# MySens-GWeasyRS485-Nano-V02-003.net
KiCad netlist of a schematic drawn in EAGLE
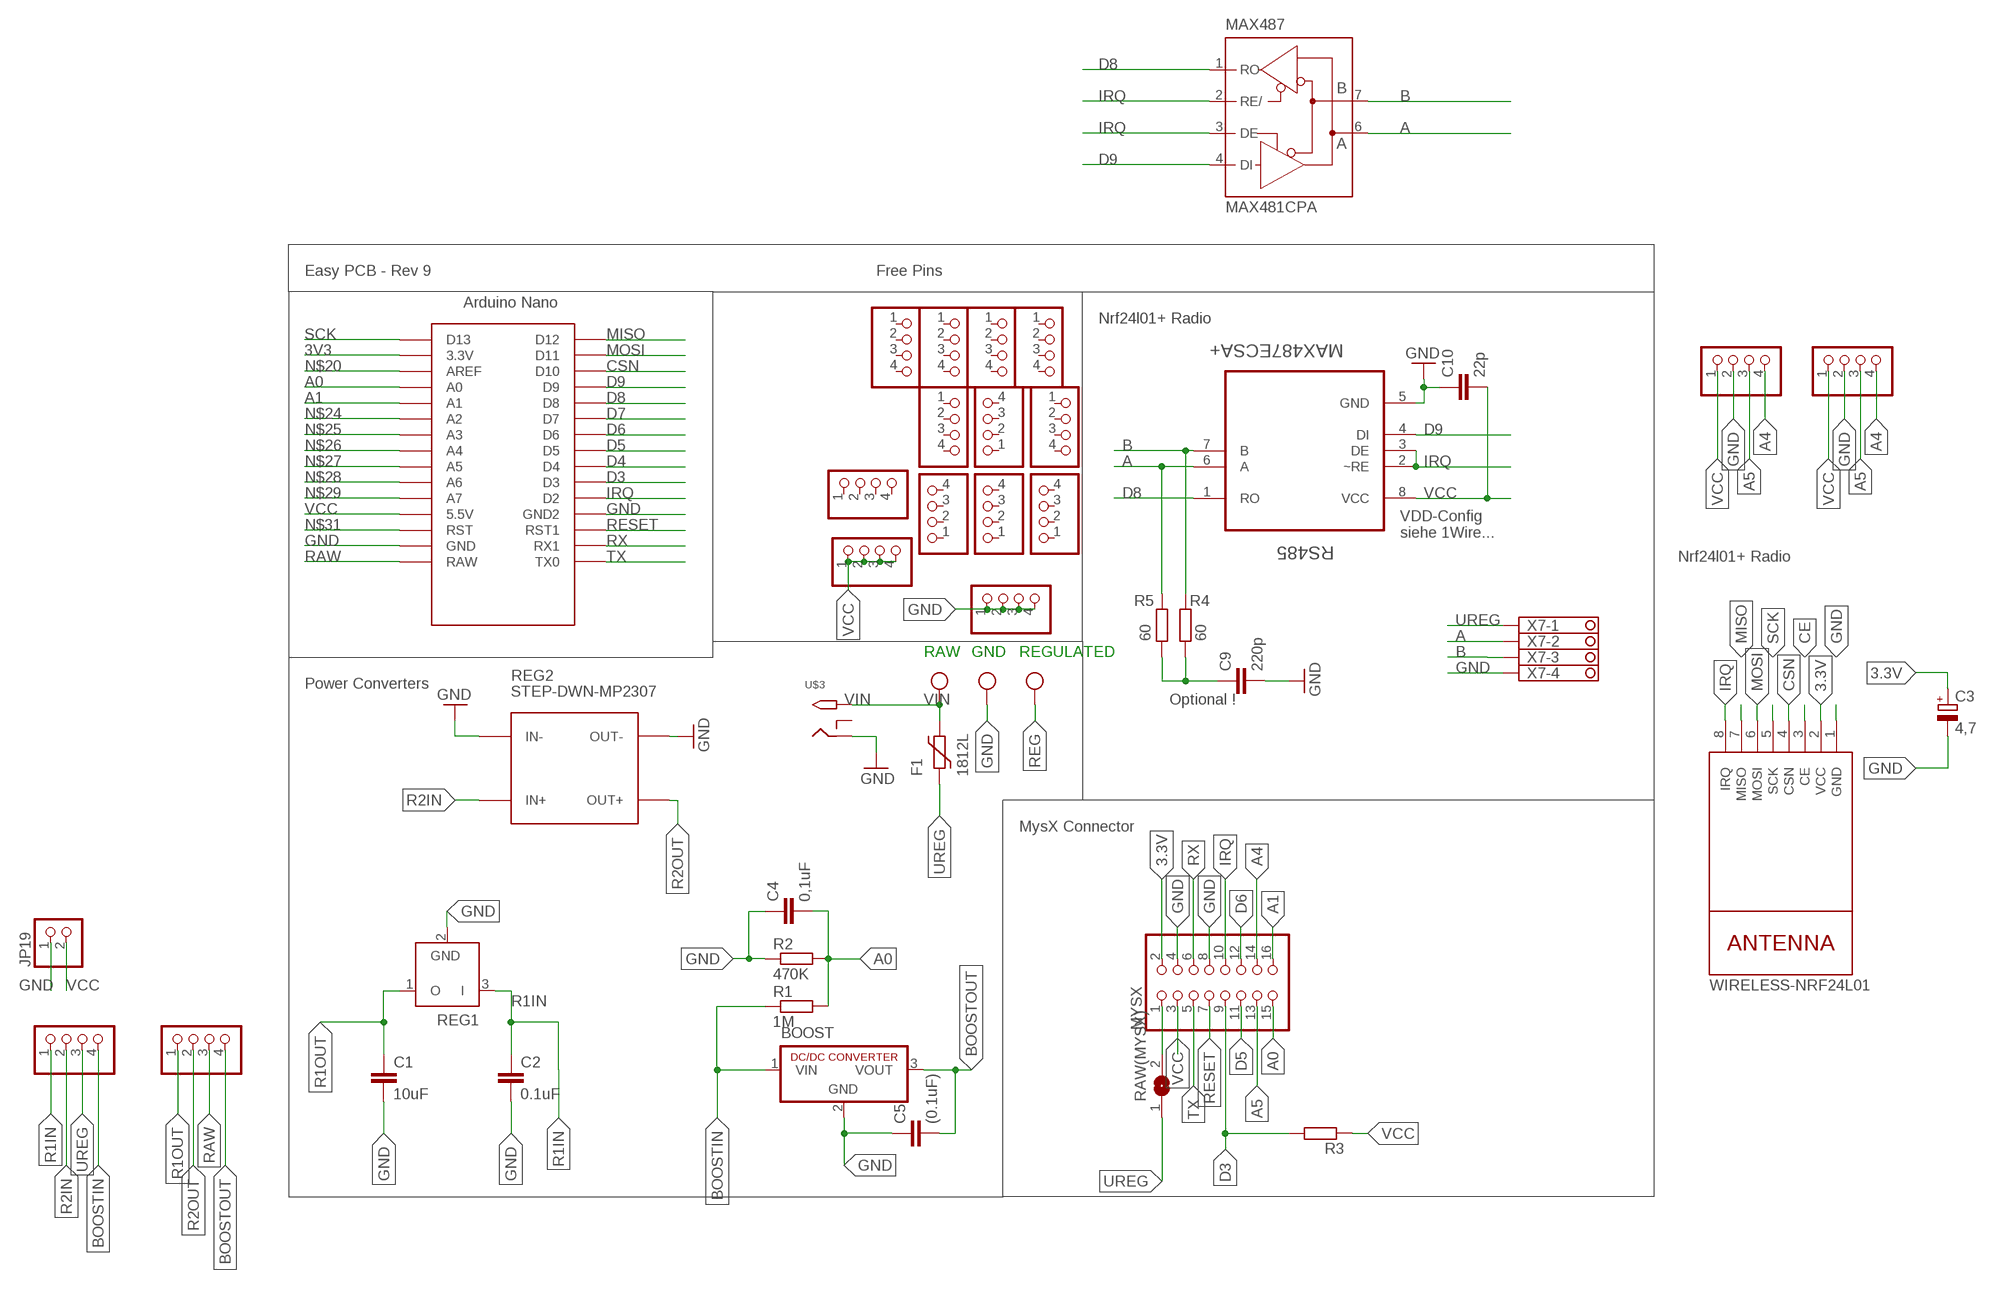
[diagram p0: schematic, sheet 1]

(export (version "E")
  (design (tool "Eeschema 10.0.6"))
  (components
    (comp (ref "BOOST")
      (value "R-78C1.8-1.0")
      (footprint "eagle-import:SIP3")
      (libsource (lib "eagle-import") (part "R-78C-1.01.8"))
    )
    (comp (ref "C1")
      (value "10uF")
      (footprint "eagle-import:C1210")
      (libsource (lib "eagle-import") (part "C-EUC1210"))
    )
    (comp (ref "C2")
      (value "0.1uF")
      (footprint "eagle-import:C1206")
      (libsource (lib "eagle-import") (part "C-EUC1206"))
    )
    (comp (ref "C3")
      (value "4,7")
      (footprint "eagle-import:SMC_C")
      (libsource (lib "eagle-import") (part "CPOL-EUSMCC"))
    )
    (comp (ref "C4")
      (value "0,1uF")
      (footprint "eagle-import:C1206")
      (libsource (lib "eagle-import") (part "C-EUC1206"))
    )
    (comp (ref "C5")
      (value "(0.1uF)")
      (footprint "eagle-import:C1206")
      (libsource (lib "eagle-import") (part "C-EUC1206"))
    )
    (comp (ref "C9")
      (value "220p")
      (footprint "eagle-import:C0805")
      (libsource (lib "eagle-import") (part "C-EUC0805"))
    )
    (comp (ref "C10")
      (value "22p")
      (footprint "eagle-import:C0805")
      (libsource (lib "eagle-import") (part "C-EUC0805"))
    )
    (comp (ref "F1")
      (value "1812L")
      (footprint "eagle-import:1812L")
      (libsource (lib "eagle-import") (part "1812L"))
    )
    (comp (ref "JP1")
      (value "PINHD-1X04_2.54-S")
      (footprint "eagle-import:1X04-S")
      (libsource (lib "eagle-import") (part "PINHD-1X04_2.54-S"))
    )
    (comp (ref "JP2")
      (value "PINHD-1X04_2.54-S")
      (footprint "eagle-import:1X04-S")
      (libsource (lib "eagle-import") (part "PINHD-1X04_2.54-S"))
    )
    (comp (ref "JP3")
      (value "PINHD-1X04_2.54-S")
      (footprint "eagle-import:1X04-S")
      (libsource (lib "eagle-import") (part "PINHD-1X04_2.54-S"))
    )
    (comp (ref "JP4")
      (value "PINHD-1X04_2.54-S")
      (footprint "eagle-import:1X04-S")
      (libsource (lib "eagle-import") (part "PINHD-1X04_2.54-S"))
    )
    (comp (ref "JP5")
      (value "PINHD-1X04_2.54-S")
      (footprint "eagle-import:1X04-S")
      (libsource (lib "eagle-import") (part "PINHD-1X04_2.54-S"))
    )
    (comp (ref "JP6")
      (value "PINHD-1X04_2.54-S")
      (footprint "eagle-import:1X04-S")
      (libsource (lib "eagle-import") (part "PINHD-1X04_2.54-S"))
    )
    (comp (ref "JP7")
      (value "PINHD-1X04_2.54-S")
      (footprint "eagle-import:1X04-S")
      (libsource (lib "eagle-import") (part "PINHD-1X04_2.54-S"))
    )
    (comp (ref "JP9")
      (value "PINHD-1X04_2.54-S")
      (footprint "eagle-import:1X04-S")
      (libsource (lib "eagle-import") (part "PINHD-1X04_2.54-S"))
    )
    (comp (ref "JP10")
      (value "PINHD-1X04_2.54-S")
      (footprint "eagle-import:1X04-S")
      (libsource (lib "eagle-import") (part "PINHD-1X04_2.54-S"))
    )
    (comp (ref "JP11")
      (value "PINHD-1X04_2.54-S")
      (footprint "eagle-import:1X04-S")
      (libsource (lib "eagle-import") (part "PINHD-1X04_2.54-S"))
    )
    (comp (ref "JP12")
      (value "PINHD-1X04_2.54-S")
      (footprint "eagle-import:1X04-S")
      (libsource (lib "eagle-import") (part "PINHD-1X04_2.54-S"))
    )
    (comp (ref "JP13")
      (value "PINHD-1X04_2.54-S")
      (footprint "eagle-import:1X04-S")
      (libsource (lib "eagle-import") (part "PINHD-1X04_2.54-S"))
    )
    (comp (ref "JP14")
      (value "PINHD-1X04_2.54-S")
      (footprint "eagle-import:1X04-S")
      (libsource (lib "eagle-import") (part "PINHD-1X04_2.54-S"))
    )
    (comp (ref "JP15")
      (value "PINHD-1X04_2.54-S")
      (footprint "eagle-import:1X04-S")
      (libsource (lib "eagle-import") (part "PINHD-1X04_2.54-S"))
    )
    (comp (ref "JP16")
      (value "PINHD-1X04_2.54-S")
      (footprint "eagle-import:1X04-S")
      (libsource (lib "eagle-import") (part "PINHD-1X04_2.54-S"))
    )
    (comp (ref "JP17")
      (value "PINHD-1X04_2.54-S")
      (footprint "eagle-import:1X04-S")
      (libsource (lib "eagle-import") (part "PINHD-1X04_2.54-S"))
    )
    (comp (ref "JP18")
      (value "PINHD-1X04_2.54-S")
      (footprint "eagle-import:1X04-S")
      (libsource (lib "eagle-import") (part "PINHD-1X04_2.54-S"))
    )
    (comp (ref "JP19")
      (value "PINHD-1X2")
      (footprint "eagle-import:1X02")
      (libsource (lib "eagle-import") (part "PINHD-1X2"))
    )
    (comp (ref "MAX487")
      (value "MAX481CPA")
      (footprint "eagle-import:DIL08")
      (libsource (lib "eagle-import") (part "MAX481CPA"))
    )
    (comp (ref "MYSX")
      (value "PINHD-2X08_2.54")
      (footprint "eagle-import:2X08")
      (libsource (lib "eagle-import") (part "PINHD-2X08_2.54"))
    )
    (comp (ref "NRF24L01+")
      (value "WIRELESS-NRF24L01")
      (footprint "eagle-import:WIRELESS-NRF24L01")
      (libsource (lib "eagle-import") (part "WIRELESS-NRF24L01"))
    )
    (comp (ref "R1")
      (value "1M")
      (footprint "eagle-import:R0805")
      (libsource (lib "eagle-import") (part "R-EU_R0805"))
    )
    (comp (ref "R2")
      (value "470K")
      (footprint "eagle-import:R0805")
      (libsource (lib "eagle-import") (part "R-EU_R0805"))
    )
    (comp (ref "R3")
      (value "R-EU_R0805")
      (footprint "eagle-import:R0805")
      (libsource (lib "eagle-import") (part "R-EU_R0805"))
    )
    (comp (ref "R4")
      (value "60")
      (footprint "eagle-import:R0805")
      (libsource (lib "eagle-import") (part "R-EU_R0805"))
    )
    (comp (ref "R5")
      (value "60")
      (footprint "eagle-import:R0805")
      (libsource (lib "eagle-import") (part "R-EU_R0805"))
    )
    (comp (ref "RAW(MYSX)")
      (value "SJ")
      (footprint "eagle-import:SJ")
      (libsource (lib "eagle-import") (part "SJ"))
    )
    (comp (ref "REG1")
      (value "LP2950Z")
      (footprint "eagle-import:TO92")
      (libsource (lib "eagle-import") (part "LP2950Z"))
    )
    (comp (ref "REG2")
      (value "STEP-DWN-MP2307")
      (footprint "eagle-import:DC-DC-STEP-DOWN-MP2307")
      (libsource (lib "eagle-import") (part "DC-DC-STEP-DOWN-MP2307"))
    )
    (comp (ref "REGULATED")
      (value "W237-103")
      (footprint "eagle-import:W237-103")
      (fields (field (name "MPN") "237-103"))
      (libsource (lib "eagle-import") (part "W237-103"))
    )
    (comp (ref "RS485")
      (value "MAX487ECSA+")
      (footprint "eagle-import:SOIC127P600X175-8N")
      (libsource (lib "eagle-import") (part "MAX487ECSA+"))
    )
    (comp (ref "U$2")
      (value "NANO")
      (footprint "eagle-import:NANO")
      (libsource (lib "eagle-import") (part "NANO"))
    )
    (comp (ref "U$3")
      (value "2.1MMJACKTHM")
      (footprint "eagle-import:PJ-102A")
      (libsource (lib "eagle-import") (part "2.1MMJACKTHM"))
    )
    (comp (ref "X7")
      (value "1751264")
      (footprint "eagle-import:1751264")
      (libsource (lib "eagle-import") (part "1751264"))
    )
  )
  (nets
    (net (code "1") (name "/3V3") (class "Default")
      (node (ref "U$2") (pin "3.3V") (pinfunction "3.3V_3.3V") (pintype "bidirectional"))
    )
    (net (code "2") (name "/A") (class "Default")
      (node (ref "MAX487") (pin "6") (pinfunction "A_6") (pintype "passive"))
      (node (ref "R5") (pin "2") (pinfunction "2_2") (pintype "passive"))
      (node (ref "RS485") (pin "6") (pinfunction "A_6") (pintype "bidirectional"))
      (node (ref "X7") (pin "2") (pinfunction "K_2") (pintype "passive"))
    )
    (net (code "3") (name "/B") (class "Default")
      (node (ref "MAX487") (pin "7") (pinfunction "B_7") (pintype "passive"))
      (node (ref "R4") (pin "2") (pinfunction "2_2") (pintype "passive"))
      (node (ref "RS485") (pin "7") (pinfunction "B_7") (pintype "bidirectional"))
      (node (ref "X7") (pin "3") (pinfunction "K_3") (pintype "passive"))
    )
    (net (code "4") (name "/D4") (class "Default")
      (node (ref "U$2") (pin "D4") (pinfunction "D4_D4") (pintype "bidirectional"))
    )
    (net (code "5") (name "/D7") (class "Default")
      (node (ref "U$2") (pin "D7") (pinfunction "D7_D7") (pintype "bidirectional"))
    )
    (net (code "6") (name "/D8") (class "Default")
      (node (ref "MAX487") (pin "1") (pinfunction "RO_1") (pintype "output"))
      (node (ref "RS485") (pin "1") (pinfunction "RO_1") (pintype "output"))
      (node (ref "U$2") (pin "D8") (pinfunction "D8_D8") (pintype "bidirectional"))
    )
    (net (code "7") (name "/D9") (class "Default")
      (node (ref "MAX487") (pin "4") (pinfunction "DI_4") (pintype "input"))
      (node (ref "RS485") (pin "4") (pinfunction "DI_4") (pintype "input"))
      (node (ref "U$2") (pin "D9") (pinfunction "D9_D9") (pintype "bidirectional"))
    )
    (net (code "8") (name "/N$20") (class "Default")
      (node (ref "U$2") (pin "AREF") (pinfunction "AREF_AREF") (pintype "bidirectional"))
    )
    (net (code "9") (name "/N$24") (class "Default")
      (node (ref "U$2") (pin "A2") (pinfunction "A2_A2") (pintype "bidirectional"))
    )
    (net (code "10") (name "/N$25") (class "Default")
      (node (ref "U$2") (pin "A3") (pinfunction "A3_A3") (pintype "bidirectional"))
    )
    (net (code "11") (name "/N$26") (class "Default")
      (node (ref "U$2") (pin "A4") (pinfunction "A4_A4") (pintype "bidirectional"))
    )
    (net (code "12") (name "/N$27") (class "Default")
      (node (ref "U$2") (pin "A5") (pinfunction "A5_A5") (pintype "bidirectional"))
    )
    (net (code "13") (name "/N$28") (class "Default")
      (node (ref "U$2") (pin "A6") (pinfunction "A6_A6") (pintype "bidirectional"))
    )
    (net (code "14") (name "/N$29") (class "Default")
      (node (ref "U$2") (pin "A7") (pinfunction "A7_A7") (pintype "bidirectional"))
    )
    (net (code "15") (name "/N$31") (class "Default")
      (node (ref "U$2") (pin "RST") (pinfunction "RST_RST") (pintype "bidirectional"))
    )
    (net (code "16") (name "/VIN") (class "Default")
      (node (ref "F1") (pin "P$2") (pinfunction "2_P$2") (pintype "passive"))
      (node (ref "REGULATED") (pin "3") (pinfunction "KL_3") (pintype "passive"))
      (node (ref "U$3") (pin "TIP") (pinfunction "TIP_TIP") (pintype "bidirectional"))
    )
    (net (code "17") (name "3.3V") (class "Default")
      (node (ref "C3") (pin "+") (pinfunction "+_+") (pintype "passive"))
      (node (ref "MYSX") (pin "2") (pinfunction "2_2") (pintype "passive"))
      (node (ref "NRF24L01+") (pin "2") (pinfunction "VCC_2") (pintype "power_in"))
    )
    (net (code "18") (name "A0") (class "Default")
      (node (ref "C4") (pin "2") (pinfunction "2_2") (pintype "passive"))
      (node (ref "MYSX") (pin "15") (pinfunction "15_15") (pintype "passive"))
      (node (ref "R1") (pin "2") (pinfunction "2_2") (pintype "passive"))
      (node (ref "R2") (pin "2") (pinfunction "2_2") (pintype "passive"))
      (node (ref "U$2") (pin "A0") (pinfunction "A0_A0") (pintype "bidirectional"))
    )
    (net (code "19") (name "A1") (class "Default")
      (node (ref "MYSX") (pin "16") (pinfunction "16_16") (pintype "passive"))
      (node (ref "U$2") (pin "A1") (pinfunction "A1_A1") (pintype "bidirectional"))
    )
    (net (code "20") (name "A4") (class "Default")
      (node (ref "JP10") (pin "4") (pinfunction "4_4") (pintype "passive"))
      (node (ref "JP6") (pin "4") (pinfunction "4_4") (pintype "passive"))
      (node (ref "MYSX") (pin "14") (pinfunction "14_14") (pintype "passive"))
    )
    (net (code "21") (name "A5") (class "Default")
      (node (ref "JP10") (pin "3") (pinfunction "3_3") (pintype "passive"))
      (node (ref "JP6") (pin "3") (pinfunction "3_3") (pintype "passive"))
      (node (ref "MYSX") (pin "13") (pinfunction "13_13") (pintype "passive"))
    )
    (net (code "22") (name "BOOSTIN") (class "Default")
      (node (ref "BOOST") (pin "1") (pinfunction "VIN_1") (pintype "passive"))
      (node (ref "JP2") (pin "4") (pinfunction "4_4") (pintype "passive"))
      (node (ref "R1") (pin "1") (pinfunction "1_1") (pintype "passive"))
    )
    (net (code "23") (name "BOOSTOUT") (class "Default")
      (node (ref "BOOST") (pin "3") (pinfunction "VOUT_3") (pintype "passive"))
      (node (ref "C5") (pin "2") (pinfunction "2_2") (pintype "passive"))
      (node (ref "JP4") (pin "4") (pinfunction "4_4") (pintype "passive"))
    )
    (net (code "24") (name "CE") (class "Default")
      (node (ref "NRF24L01+") (pin "3") (pinfunction "CE_3") (pintype "bidirectional"))
    )
    (net (code "25") (name "CSN") (class "Default")
      (node (ref "NRF24L01+") (pin "4") (pinfunction "CSN_4") (pintype "bidirectional"))
      (node (ref "U$2") (pin "D10") (pinfunction "D10_D10") (pintype "bidirectional"))
    )
    (net (code "26") (name "D3") (class "Default")
      (node (ref "MYSX") (pin "9") (pinfunction "9_9") (pintype "passive"))
      (node (ref "R3") (pin "2") (pinfunction "2_2") (pintype "passive"))
      (node (ref "U$2") (pin "D3") (pinfunction "D3_D3") (pintype "bidirectional"))
    )
    (net (code "27") (name "D5") (class "Default")
      (node (ref "MYSX") (pin "11") (pinfunction "11_11") (pintype "passive"))
      (node (ref "U$2") (pin "D5") (pinfunction "D5_D5") (pintype "bidirectional"))
    )
    (net (code "28") (name "D6") (class "Default")
      (node (ref "MYSX") (pin "12") (pinfunction "12_12") (pintype "passive"))
      (node (ref "U$2") (pin "D6") (pinfunction "D6_D6") (pintype "bidirectional"))
    )
    (net (code "29") (name "GND") (class "Default")
      (node (ref "BOOST") (pin "2") (pinfunction "GND_2") (pintype "passive"))
      (node (ref "C1") (pin "2") (pinfunction "2_2") (pintype "passive"))
      (node (ref "C10") (pin "1") (pinfunction "1_1") (pintype "passive"))
      (node (ref "C2") (pin "2") (pinfunction "2_2") (pintype "passive"))
      (node (ref "C3") (pin "-") (pinfunction "-_-") (pintype "passive"))
      (node (ref "C4") (pin "1") (pinfunction "1_1") (pintype "passive"))
      (node (ref "C5") (pin "1") (pinfunction "1_1") (pintype "passive"))
      (node (ref "C9") (pin "2") (pinfunction "2_2") (pintype "passive"))
      (node (ref "JP1") (pin "1") (pinfunction "1_1") (pintype "passive"))
      (node (ref "JP1") (pin "2") (pinfunction "2_2") (pintype "passive"))
      (node (ref "JP1") (pin "3") (pinfunction "3_3") (pintype "passive"))
      (node (ref "JP1") (pin "4") (pinfunction "4_4") (pintype "passive"))
      (node (ref "JP10") (pin "2") (pinfunction "2_2") (pintype "passive"))
      (node (ref "JP19") (pin "1") (pinfunction "1_1") (pintype "passive"))
      (node (ref "JP6") (pin "2") (pinfunction "2_2") (pintype "passive"))
      (node (ref "MYSX") (pin "4") (pinfunction "4_4") (pintype "passive"))
      (node (ref "MYSX") (pin "8") (pinfunction "8_8") (pintype "passive"))
      (node (ref "NRF24L01+") (pin "1") (pinfunction "GND_1") (pintype "power_in"))
      (node (ref "R2") (pin "1") (pinfunction "1_1") (pintype "passive"))
      (node (ref "REG1") (pin "2") (pinfunction "GND_2") (pintype "power_in"))
      (node (ref "REG2") (pin "IN-") (pinfunction "IN-_IN-") (pintype "bidirectional"))
      (node (ref "REG2") (pin "OUT-") (pinfunction "OUT-_OUT-") (pintype "bidirectional"))
      (node (ref "REGULATED") (pin "2") (pinfunction "KL_2") (pintype "passive"))
      (node (ref "RS485") (pin "5") (pinfunction "GND_5") (pintype "passive"))
      (node (ref "U$2") (pin "GND") (pinfunction "GND_GND") (pintype "bidirectional"))
      (node (ref "U$2") (pin "GND1") (pinfunction "GND2_GND1") (pintype "bidirectional"))
      (node (ref "U$3") (pin "RING") (pinfunction "RING_RING") (pintype "bidirectional"))
      (node (ref "X7") (pin "4") (pinfunction "K_4") (pintype "passive"))
    )
    (net (code "30") (name "IRQ") (class "Default")
      (node (ref "MAX487") (pin "2") (pinfunction "RE/_2") (pintype "input"))
      (node (ref "MAX487") (pin "3") (pinfunction "DE_3") (pintype "input"))
      (node (ref "MYSX") (pin "10") (pinfunction "10_10") (pintype "passive"))
      (node (ref "NRF24L01+") (pin "8") (pinfunction "IRQ_8") (pintype "bidirectional"))
      (node (ref "RS485") (pin "2") (pinfunction "~{RE}_2") (pintype "input"))
      (node (ref "RS485") (pin "3") (pinfunction "DE_3") (pintype "input"))
      (node (ref "U$2") (pin "D2") (pinfunction "D2_D2") (pintype "bidirectional"))
    )
    (net (code "31") (name "MISO") (class "Default")
      (node (ref "NRF24L01+") (pin "7") (pinfunction "MISO_7") (pintype "bidirectional"))
      (node (ref "U$2") (pin "D12") (pinfunction "D12_D12") (pintype "bidirectional"))
    )
    (net (code "32") (name "MOSI") (class "Default")
      (node (ref "NRF24L01+") (pin "6") (pinfunction "MOSI_6") (pintype "bidirectional"))
      (node (ref "U$2") (pin "D11") (pinfunction "D11_D11") (pintype "bidirectional"))
    )
    (net (code "33") (name "Net-(C9-Pad1)") (class "Default")
      (node (ref "C9") (pin "1") (pinfunction "1_1") (pintype "passive"))
      (node (ref "R4") (pin "1") (pinfunction "1_1") (pintype "passive"))
      (node (ref "R5") (pin "1") (pinfunction "1_1") (pintype "passive"))
    )
    (net (code "34") (name "Net-(MYSX-Pad1)") (class "Default")
      (node (ref "MYSX") (pin "1") (pinfunction "1_1") (pintype "passive"))
      (node (ref "RAW(MYSX)") (pin "2") (pinfunction "2_2") (pintype "passive"))
    )
    (net (code "35") (name "R1IN") (class "Default")
      (node (ref "C2") (pin "1") (pinfunction "1_1") (pintype "passive"))
      (node (ref "JP2") (pin "1") (pinfunction "1_1") (pintype "passive"))
      (node (ref "REG1") (pin "3") (pinfunction "I_3") (pintype "input"))
    )
    (net (code "36") (name "R1OUT") (class "Default")
      (node (ref "C1") (pin "1") (pinfunction "1_1") (pintype "passive"))
      (node (ref "JP4") (pin "1") (pinfunction "1_1") (pintype "passive"))
      (node (ref "REG1") (pin "1") (pinfunction "O_1") (pintype "input"))
    )
    (net (code "37") (name "R2IN") (class "Default")
      (node (ref "JP2") (pin "2") (pinfunction "2_2") (pintype "passive"))
      (node (ref "REG2") (pin "IN+") (pinfunction "IN+_IN+") (pintype "bidirectional"))
    )
    (net (code "38") (name "R2OUT") (class "Default")
      (node (ref "JP4") (pin "2") (pinfunction "2_2") (pintype "passive"))
      (node (ref "REG2") (pin "OUT+") (pinfunction "OUT+_OUT+") (pintype "bidirectional"))
    )
    (net (code "39") (name "RAW") (class "Default")
      (node (ref "JP4") (pin "3") (pinfunction "3_3") (pintype "passive"))
      (node (ref "U$2") (pin "RAW") (pinfunction "RAW_RAW") (pintype "bidirectional"))
    )
    (net (code "40") (name "REG") (class "Default")
      (node (ref "REGULATED") (pin "1") (pinfunction "KL_1") (pintype "passive"))
    )
    (net (code "41") (name "RESET") (class "Default")
      (node (ref "MYSX") (pin "7") (pinfunction "7_7") (pintype "passive"))
      (node (ref "U$2") (pin "RST1") (pinfunction "RST1_RST1") (pintype "bidirectional"))
    )
    (net (code "42") (name "RX") (class "Default")
      (node (ref "MYSX") (pin "6") (pinfunction "6_6") (pintype "passive"))
      (node (ref "U$2") (pin "RX1") (pinfunction "RX1_RX1") (pintype "bidirectional"))
    )
    (net (code "43") (name "SCK") (class "Default")
      (node (ref "NRF24L01+") (pin "5") (pinfunction "SCK_5") (pintype "bidirectional"))
      (node (ref "U$2") (pin "D13") (pinfunction "D13_D13") (pintype "bidirectional"))
    )
    (net (code "44") (name "TX") (class "Default")
      (node (ref "MYSX") (pin "5") (pinfunction "5_5") (pintype "passive"))
      (node (ref "U$2") (pin "TX0") (pinfunction "TX0_TX0") (pintype "bidirectional"))
    )
    (net (code "45") (name "UREG") (class "Default")
      (node (ref "F1") (pin "P$1") (pinfunction "1_P$1") (pintype "passive"))
      (node (ref "JP2") (pin "3") (pinfunction "3_3") (pintype "passive"))
      (node (ref "RAW(MYSX)") (pin "1") (pinfunction "1_1") (pintype "passive"))
      (node (ref "X7") (pin "1") (pinfunction "K_1") (pintype "passive"))
    )
    (net (code "46") (name "VCC") (class "Default")
      (node (ref "C10") (pin "2") (pinfunction "2_2") (pintype "passive"))
      (node (ref "JP10") (pin "1") (pinfunction "1_1") (pintype "passive"))
      (node (ref "JP19") (pin "2") (pinfunction "2_2") (pintype "passive"))
      (node (ref "JP3") (pin "1") (pinfunction "1_1") (pintype "passive"))
      (node (ref "JP3") (pin "2") (pinfunction "2_2") (pintype "passive"))
      (node (ref "JP3") (pin "3") (pinfunction "3_3") (pintype "passive"))
      (node (ref "JP3") (pin "4") (pinfunction "4_4") (pintype "passive"))
      (node (ref "JP6") (pin "1") (pinfunction "1_1") (pintype "passive"))
      (node (ref "MYSX") (pin "3") (pinfunction "3_3") (pintype "passive"))
      (node (ref "R3") (pin "1") (pinfunction "1_1") (pintype "passive"))
      (node (ref "RS485") (pin "8") (pinfunction "VCC_8") (pintype "power_in"))
      (node (ref "U$2") (pin "5V") (pinfunction "5.5V_5V") (pintype "bidirectional"))
    )
    (net (code "47") (name "unconnected-(JP5-Pad1)") (class "Default")
      (node (ref "JP5") (pin "1") (pinfunction "1_1") (pintype "passive"))
    )
    (net (code "48") (name "unconnected-(JP5-Pad2)") (class "Default")
      (node (ref "JP5") (pin "2") (pinfunction "2_2") (pintype "passive"))
    )
    (net (code "49") (name "unconnected-(JP5-Pad3)") (class "Default")
      (node (ref "JP5") (pin "3") (pinfunction "3_3") (pintype "passive"))
    )
    (net (code "50") (name "unconnected-(JP5-Pad4)") (class "Default")
      (node (ref "JP5") (pin "4") (pinfunction "4_4") (pintype "passive"))
    )
    (net (code "51") (name "unconnected-(JP7-Pad1)") (class "Default")
      (node (ref "JP7") (pin "1") (pinfunction "1_1") (pintype "passive"))
    )
    (net (code "52") (name "unconnected-(JP7-Pad2)") (class "Default")
      (node (ref "JP7") (pin "2") (pinfunction "2_2") (pintype "passive"))
    )
    (net (code "53") (name "unconnected-(JP7-Pad3)") (class "Default")
      (node (ref "JP7") (pin "3") (pinfunction "3_3") (pintype "passive"))
    )
    (net (code "54") (name "unconnected-(JP7-Pad4)") (class "Default")
      (node (ref "JP7") (pin "4") (pinfunction "4_4") (pintype "passive"))
    )
    (net (code "55") (name "unconnected-(JP9-Pad1)") (class "Default")
      (node (ref "JP9") (pin "1") (pinfunction "1_1") (pintype "passive"))
    )
    (net (code "56") (name "unconnected-(JP9-Pad2)") (class "Default")
      (node (ref "JP9") (pin "2") (pinfunction "2_2") (pintype "passive"))
    )
    (net (code "57") (name "unconnected-(JP9-Pad3)") (class "Default")
      (node (ref "JP9") (pin "3") (pinfunction "3_3") (pintype "passive"))
    )
    (net (code "58") (name "unconnected-(JP9-Pad4)") (class "Default")
      (node (ref "JP9") (pin "4") (pinfunction "4_4") (pintype "passive"))
    )
    (net (code "59") (name "unconnected-(JP11-Pad1)") (class "Default")
      (node (ref "JP11") (pin "1") (pinfunction "1_1") (pintype "passive"))
    )
    (net (code "60") (name "unconnected-(JP11-Pad2)") (class "Default")
      (node (ref "JP11") (pin "2") (pinfunction "2_2") (pintype "passive"))
    )
    (net (code "61") (name "unconnected-(JP11-Pad3)") (class "Default")
      (node (ref "JP11") (pin "3") (pinfunction "3_3") (pintype "passive"))
    )
    (net (code "62") (name "unconnected-(JP11-Pad4)") (class "Default")
      (node (ref "JP11") (pin "4") (pinfunction "4_4") (pintype "passive"))
    )
    (net (code "63") (name "unconnected-(JP12-Pad1)") (class "Default")
      (node (ref "JP12") (pin "1") (pinfunction "1_1") (pintype "passive"))
    )
    (net (code "64") (name "unconnected-(JP12-Pad2)") (class "Default")
      (node (ref "JP12") (pin "2") (pinfunction "2_2") (pintype "passive"))
    )
    (net (code "65") (name "unconnected-(JP12-Pad3)") (class "Default")
      (node (ref "JP12") (pin "3") (pinfunction "3_3") (pintype "passive"))
    )
    (net (code "66") (name "unconnected-(JP12-Pad4)") (class "Default")
      (node (ref "JP12") (pin "4") (pinfunction "4_4") (pintype "passive"))
    )
    (net (code "67") (name "unconnected-(JP13-Pad1)") (class "Default")
      (node (ref "JP13") (pin "1") (pinfunction "1_1") (pintype "passive"))
    )
    (net (code "68") (name "unconnected-(JP13-Pad2)") (class "Default")
      (node (ref "JP13") (pin "2") (pinfunction "2_2") (pintype "passive"))
    )
    (net (code "69") (name "unconnected-(JP13-Pad3)") (class "Default")
      (node (ref "JP13") (pin "3") (pinfunction "3_3") (pintype "passive"))
    )
    (net (code "70") (name "unconnected-(JP13-Pad4)") (class "Default")
      (node (ref "JP13") (pin "4") (pinfunction "4_4") (pintype "passive"))
    )
    (net (code "71") (name "unconnected-(JP14-Pad1)") (class "Default")
      (node (ref "JP14") (pin "1") (pinfunction "1_1") (pintype "passive"))
    )
    (net (code "72") (name "unconnected-(JP14-Pad2)") (class "Default")
      (node (ref "JP14") (pin "2") (pinfunction "2_2") (pintype "passive"))
    )
    (net (code "73") (name "unconnected-(JP14-Pad3)") (class "Default")
      (node (ref "JP14") (pin "3") (pinfunction "3_3") (pintype "passive"))
    )
    (net (code "74") (name "unconnected-(JP14-Pad4)") (class "Default")
      (node (ref "JP14") (pin "4") (pinfunction "4_4") (pintype "passive"))
    )
    (net (code "75") (name "unconnected-(JP15-Pad1)") (class "Default")
      (node (ref "JP15") (pin "1") (pinfunction "1_1") (pintype "passive"))
    )
    (net (code "76") (name "unconnected-(JP15-Pad2)") (class "Default")
      (node (ref "JP15") (pin "2") (pinfunction "2_2") (pintype "passive"))
    )
    (net (code "77") (name "unconnected-(JP15-Pad3)") (class "Default")
      (node (ref "JP15") (pin "3") (pinfunction "3_3") (pintype "passive"))
    )
    (net (code "78") (name "unconnected-(JP15-Pad4)") (class "Default")
      (node (ref "JP15") (pin "4") (pinfunction "4_4") (pintype "passive"))
    )
    (net (code "79") (name "unconnected-(JP16-Pad1)") (class "Default")
      (node (ref "JP16") (pin "1") (pinfunction "1_1") (pintype "passive"))
    )
    (net (code "80") (name "unconnected-(JP16-Pad2)") (class "Default")
      (node (ref "JP16") (pin "2") (pinfunction "2_2") (pintype "passive"))
    )
    (net (code "81") (name "unconnected-(JP16-Pad3)") (class "Default")
      (node (ref "JP16") (pin "3") (pinfunction "3_3") (pintype "passive"))
    )
    (net (code "82") (name "unconnected-(JP16-Pad4)") (class "Default")
      (node (ref "JP16") (pin "4") (pinfunction "4_4") (pintype "passive"))
    )
    (net (code "83") (name "unconnected-(JP17-Pad1)") (class "Default")
      (node (ref "JP17") (pin "1") (pinfunction "1_1") (pintype "passive"))
    )
    (net (code "84") (name "unconnected-(JP17-Pad2)") (class "Default")
      (node (ref "JP17") (pin "2") (pinfunction "2_2") (pintype "passive"))
    )
    (net (code "85") (name "unconnected-(JP17-Pad3)") (class "Default")
      (node (ref "JP17") (pin "3") (pinfunction "3_3") (pintype "passive"))
    )
    (net (code "86") (name "unconnected-(JP17-Pad4)") (class "Default")
      (node (ref "JP17") (pin "4") (pinfunction "4_4") (pintype "passive"))
    )
    (net (code "87") (name "unconnected-(JP18-Pad1)") (class "Default")
      (node (ref "JP18") (pin "1") (pinfunction "1_1") (pintype "passive"))
    )
    (net (code "88") (name "unconnected-(JP18-Pad2)") (class "Default")
      (node (ref "JP18") (pin "2") (pinfunction "2_2") (pintype "passive"))
    )
    (net (code "89") (name "unconnected-(JP18-Pad3)") (class "Default")
      (node (ref "JP18") (pin "3") (pinfunction "3_3") (pintype "passive"))
    )
    (net (code "90") (name "unconnected-(JP18-Pad4)") (class "Default")
      (node (ref "JP18") (pin "4") (pinfunction "4_4") (pintype "passive"))
    )
    (net (code "91") (name "unconnected-(U$2-PadICSP1)") (class "Default")
      (node (ref "U$2") (pin "ICSP1") (pinfunction "ICSP1_ICSP1") (pintype "bidirectional"))
    )
    (net (code "92") (name "unconnected-(U$2-PadICSP2)") (class "Default")
      (node (ref "U$2") (pin "ICSP2") (pinfunction "ICSP2_ICSP2") (pintype "bidirectional"))
    )
    (net (code "93") (name "unconnected-(U$2-PadICSP3)") (class "Default")
      (node (ref "U$2") (pin "ICSP3") (pinfunction "ICSP3_ICSP3") (pintype "bidirectional"))
    )
    (net (code "94") (name "unconnected-(U$2-PadICSP4)") (class "Default")
      (node (ref "U$2") (pin "ICSP4") (pinfunction "ICSP4_ICSP4") (pintype "bidirectional"))
    )
    (net (code "95") (name "unconnected-(U$2-PadICSP5)") (class "Default")
      (node (ref "U$2") (pin "ICSP5") (pinfunction "ICSP5_ICSP5") (pintype "bidirectional"))
    )
    (net (code "96") (name "unconnected-(U$2-PadICSP6)") (class "Default")
      (node (ref "U$2") (pin "ICSP6") (pinfunction "ICSP6_ICSP6") (pintype "bidirectional"))
    )
    (net (code "97") (name "unconnected-(U$3-PadRING_SW)") (class "Default")
      (node (ref "U$3") (pin "RING_SW") (pinfunction "RING_SW_RING_SW") (pintype "bidirectional"))
    )
  )
)
